# shield_SFM10R1.net
KiCad netlist of a schematic drawn in EAGLE
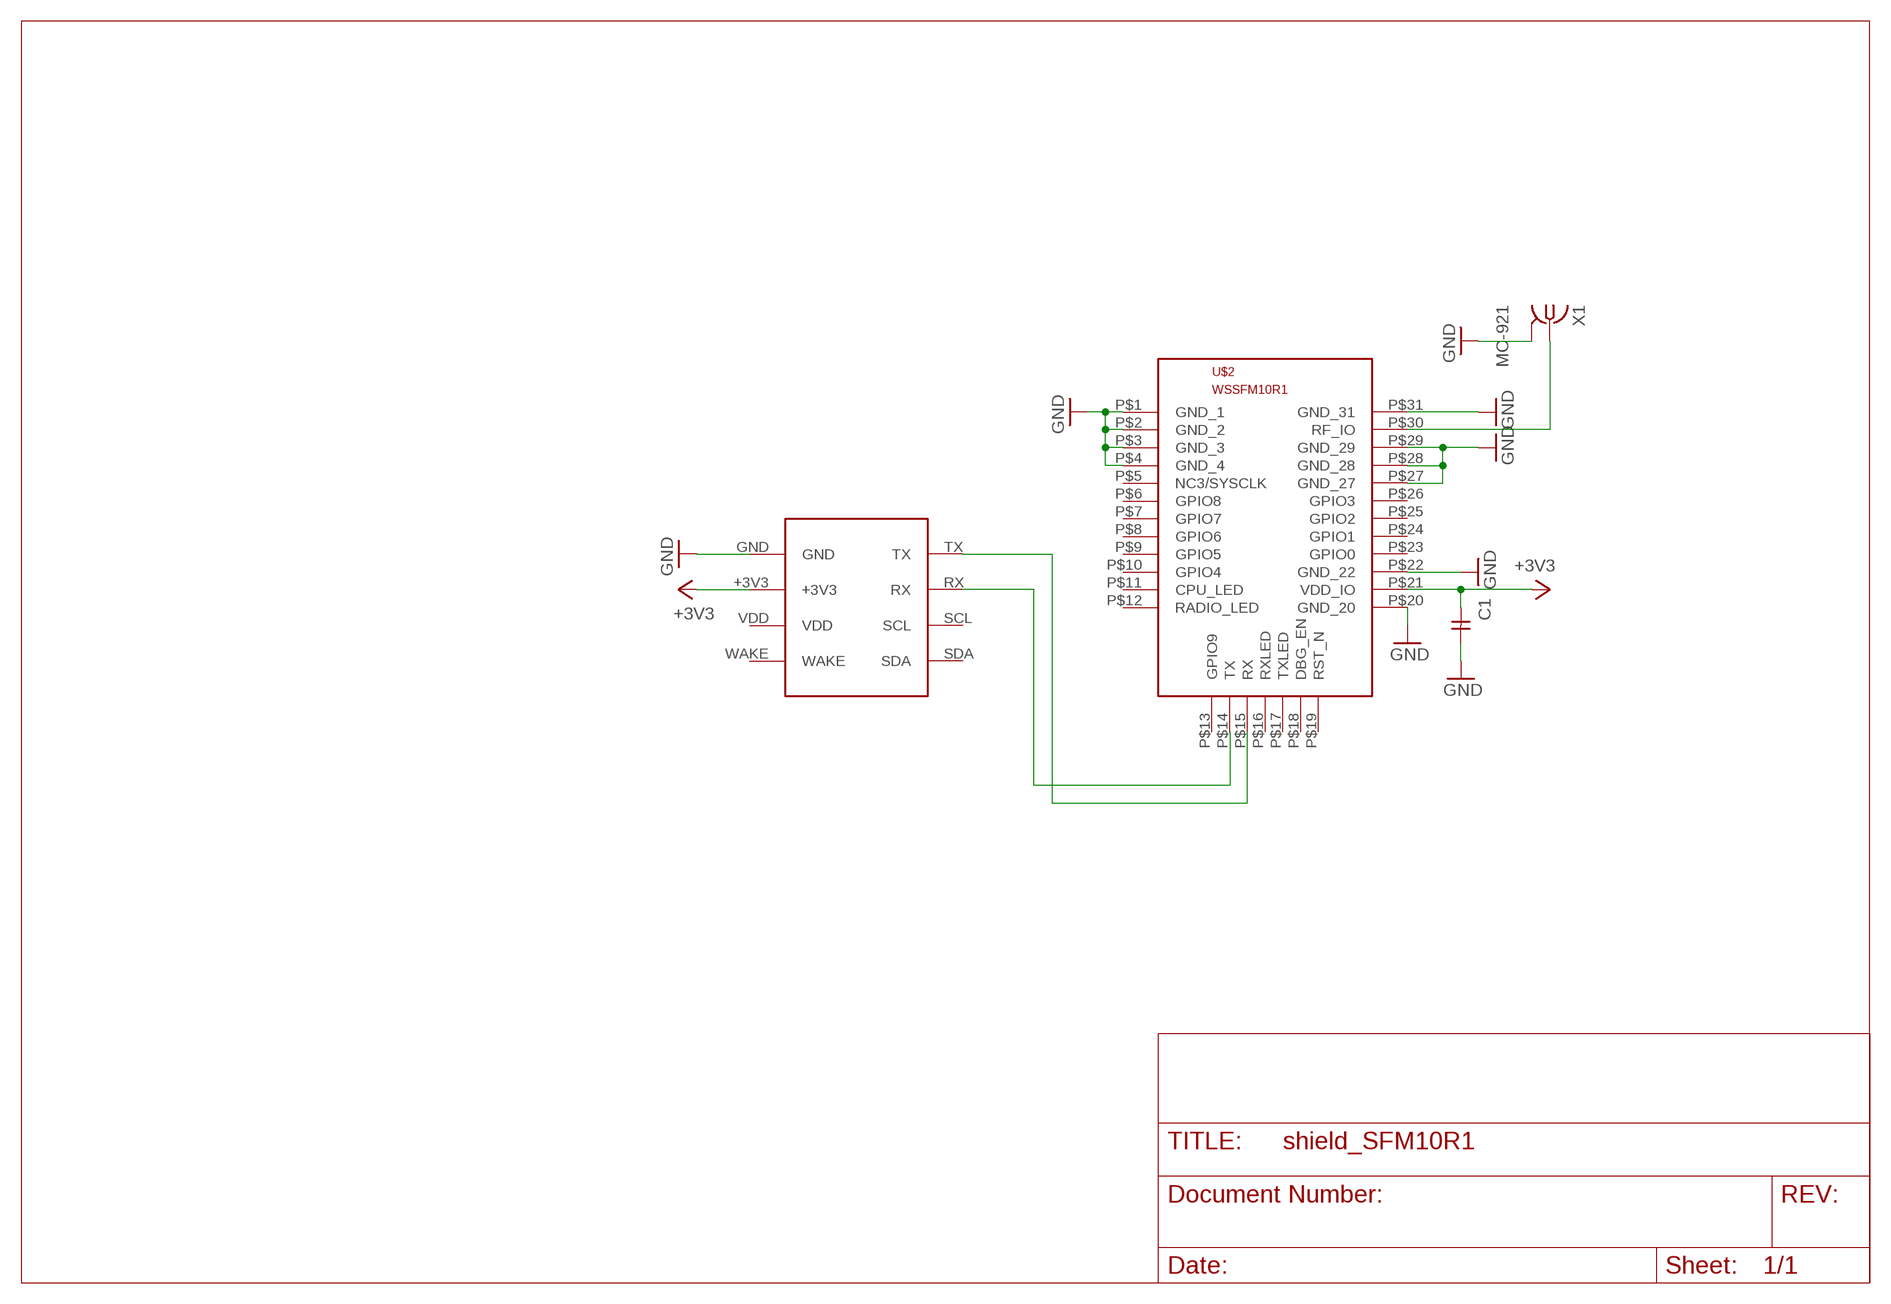
[diagram p0: schematic, sheet 1]

(export (version "E")
  (design (tool "Eeschema 10.0.6"))
  (components
    (comp (ref "C1")
      (value "CSMD_1206")
      (footprint "eagle-import:SMD_RC_1206")
      (libsource (lib "eagle-import") (part "CSMD_1206"))
    )
    (comp (ref "U$1")
      (value "SHIELD")
      (footprint "eagle-import:SHIELD")
      (libsource (lib "eagle-import") (part "SHIELD"))
    )
    (comp (ref "U$2")
      (value "SFM10R1")
      (footprint "eagle-import:SFM10R1")
      (libsource (lib "eagle-import") (part "SFM10R1"))
    )
    (comp (ref "X1")
      (value "MC-921")
      (footprint "eagle-import:MC-921")
      (libsource (lib "eagle-import") (part "MC-921"))
    )
  )
  (nets
    (net (code "1") (name "+3V3") (class "Default")
      (node (ref "C1") (pin "P$1") (pinfunction "1_P$1") (pintype "passive"))
      (node (ref "U$1") (pin "+3V3") (pinfunction "+3V3_+3V3") (pintype "power_in"))
      (node (ref "U$2") (pin "P$21") (pinfunction "VDD_IO_P$21") (pintype "bidirectional"))
    )
    (net (code "2") (name "/VDD") (class "Default")
      (node (ref "U$1") (pin "VDD") (pinfunction "VDD_VDD") (pintype "power_in"))
    )
    (net (code "3") (name "GND") (class "Default")
      (node (ref "C1") (pin "P$2") (pinfunction "2_P$2") (pintype "passive"))
      (node (ref "U$1") (pin "GND") (pinfunction "GND_GND") (pintype "power_in"))
      (node (ref "U$2") (pin "P$1") (pinfunction "GND_1_P$1") (pintype "bidirectional"))
      (node (ref "U$2") (pin "P$2") (pinfunction "GND_2_P$2") (pintype "bidirectional"))
      (node (ref "U$2") (pin "P$20") (pinfunction "GND_20_P$20") (pintype "bidirectional"))
      (node (ref "U$2") (pin "P$22") (pinfunction "GND_22_P$22") (pintype "bidirectional"))
      (node (ref "U$2") (pin "P$27") (pinfunction "GND_27_P$27") (pintype "bidirectional"))
      (node (ref "U$2") (pin "P$28") (pinfunction "GND_28_P$28") (pintype "bidirectional"))
      (node (ref "U$2") (pin "P$29") (pinfunction "GND_29_P$29") (pintype "bidirectional"))
      (node (ref "U$2") (pin "P$3") (pinfunction "GND_3_P$3") (pintype "bidirectional"))
      (node (ref "U$2") (pin "P$31") (pinfunction "GND_31_P$31") (pintype "bidirectional"))
      (node (ref "U$2") (pin "P$4") (pinfunction "GND_4_P$4") (pintype "bidirectional"))
      (node (ref "X1") (pin "2@1") (pinfunction "GND_2@1") (pintype "passive"))
      (node (ref "X1") (pin "2@2") (pinfunction "GND_2@2") (pintype "passive"))
    )
    (net (code "4") (name "Net-(U$2-RF_IO)") (class "Default")
      (node (ref "U$2") (pin "P$30") (pinfunction "RF_IO_P$30") (pintype "bidirectional"))
      (node (ref "X1") (pin "1") (pinfunction "1_1") (pintype "passive"))
    )
    (net (code "5") (name "Net-(U$2-RX)") (class "Default")
      (node (ref "U$1") (pin "TX") (pinfunction "TX_TX") (pintype "output"))
      (node (ref "U$2") (pin "P$15") (pinfunction "RX_P$15") (pintype "bidirectional"))
    )
    (net (code "6") (name "Net-(U$2-TX)") (class "Default")
      (node (ref "U$1") (pin "RX") (pinfunction "RX_RX") (pintype "input"))
      (node (ref "U$2") (pin "P$14") (pinfunction "TX_P$14") (pintype "bidirectional"))
    )
    (net (code "7") (name "unconnected-(U$1-PadSCL)") (class "Default")
      (node (ref "U$1") (pin "SCL") (pinfunction "SCL_SCL") (pintype "output"))
    )
    (net (code "8") (name "unconnected-(U$1-PadSDA)") (class "Default")
      (node (ref "U$1") (pin "SDA") (pinfunction "SDA_SDA") (pintype "bidirectional"))
    )
    (net (code "9") (name "unconnected-(U$1-PadWAKE)") (class "Default")
      (node (ref "U$1") (pin "WAKE") (pinfunction "WAKE_WAKE") (pintype "output"))
    )
    (net (code "10") (name "unconnected-(U$2-CPU_LED-PadP$11)") (class "Default")
      (node (ref "U$2") (pin "P$11") (pinfunction "CPU_LED_P$11") (pintype "bidirectional"))
    )
    (net (code "11") (name "unconnected-(U$2-DBG_EN-PadP$18)") (class "Default")
      (node (ref "U$2") (pin "P$18") (pinfunction "DBG_EN_P$18") (pintype "bidirectional"))
    )
    (net (code "12") (name "unconnected-(U$2-GPIO0-PadP$23)") (class "Default")
      (node (ref "U$2") (pin "P$23") (pinfunction "GPIO0_P$23") (pintype "bidirectional"))
    )
    (net (code "13") (name "unconnected-(U$2-GPIO1-PadP$24)") (class "Default")
      (node (ref "U$2") (pin "P$24") (pinfunction "GPIO1_P$24") (pintype "bidirectional"))
    )
    (net (code "14") (name "unconnected-(U$2-GPIO2-PadP$25)") (class "Default")
      (node (ref "U$2") (pin "P$25") (pinfunction "GPIO2_P$25") (pintype "bidirectional"))
    )
    (net (code "15") (name "unconnected-(U$2-GPIO3-PadP$26)") (class "Default")
      (node (ref "U$2") (pin "P$26") (pinfunction "GPIO3_P$26") (pintype "bidirectional"))
    )
    (net (code "16") (name "unconnected-(U$2-GPIO4-PadP$10)") (class "Default")
      (node (ref "U$2") (pin "P$10") (pinfunction "GPIO4_P$10") (pintype "bidirectional"))
    )
    (net (code "17") (name "unconnected-(U$2-GPIO5-PadP$9)") (class "Default")
      (node (ref "U$2") (pin "P$9") (pinfunction "GPIO5_P$9") (pintype "bidirectional"))
    )
    (net (code "18") (name "unconnected-(U$2-GPIO6-PadP$8)") (class "Default")
      (node (ref "U$2") (pin "P$8") (pinfunction "GPIO6_P$8") (pintype "bidirectional"))
    )
    (net (code "19") (name "unconnected-(U$2-GPIO7-PadP$7)") (class "Default")
      (node (ref "U$2") (pin "P$7") (pinfunction "GPIO7_P$7") (pintype "bidirectional"))
    )
    (net (code "20") (name "unconnected-(U$2-GPIO8-PadP$6)") (class "Default")
      (node (ref "U$2") (pin "P$6") (pinfunction "GPIO8_P$6") (pintype "bidirectional"))
    )
    (net (code "21") (name "unconnected-(U$2-GPIO9-PadP$13)") (class "Default")
      (node (ref "U$2") (pin "P$13") (pinfunction "GPIO9_P$13") (pintype "bidirectional"))
    )
    (net (code "22") (name "unconnected-(U$2-NC3{slash}SYSCLK-PadP$5)") (class "Default")
      (node (ref "U$2") (pin "P$5") (pinfunction "NC3/SYSCLK_P$5") (pintype "bidirectional"))
    )
    (net (code "23") (name "unconnected-(U$2-RADIO_LED-PadP$12)") (class "Default")
      (node (ref "U$2") (pin "P$12") (pinfunction "RADIO_LED_P$12") (pintype "bidirectional"))
    )
    (net (code "24") (name "unconnected-(U$2-RST_N-PadP$19)") (class "Default")
      (node (ref "U$2") (pin "P$19") (pinfunction "RST_N_P$19") (pintype "bidirectional"))
    )
    (net (code "25") (name "unconnected-(U$2-RXLED-PadP$16)") (class "Default")
      (node (ref "U$2") (pin "P$16") (pinfunction "RXLED_P$16") (pintype "bidirectional"))
    )
    (net (code "26") (name "unconnected-(U$2-TXLED-PadP$17)") (class "Default")
      (node (ref "U$2") (pin "P$17") (pinfunction "TXLED_P$17") (pintype "bidirectional"))
    )
  )
)
